# Connectors.net
KiCad netlist of a schematic drawn in Altium Designer
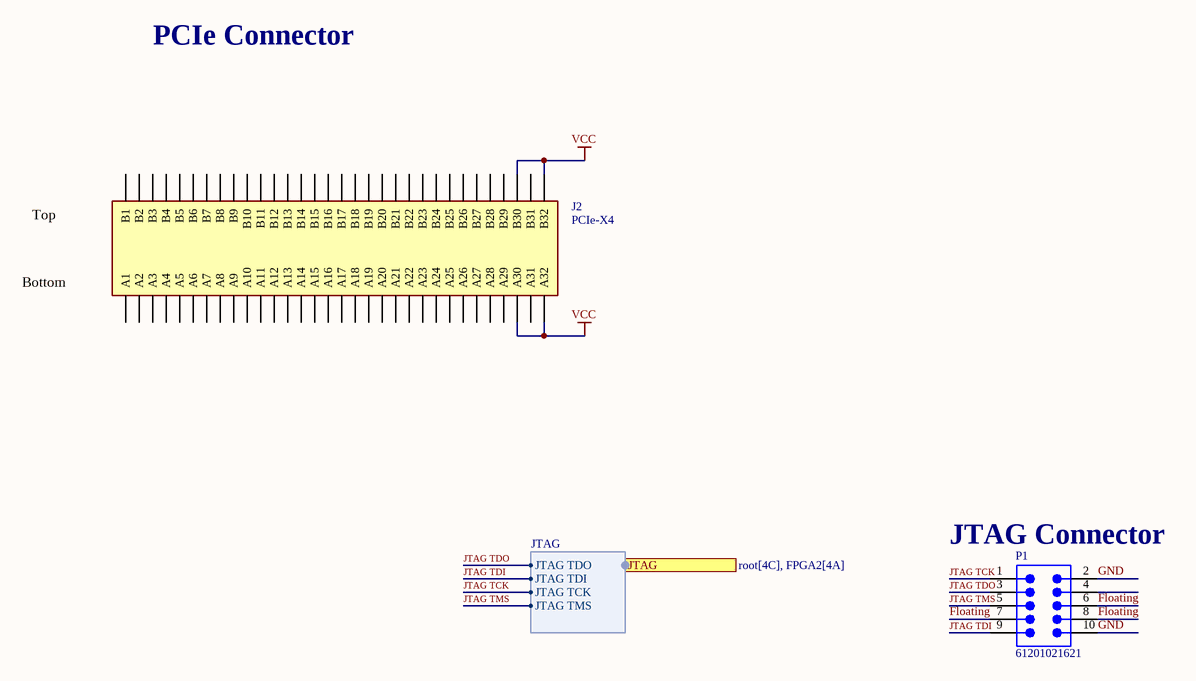
[diagram p0: Connectors.SchDoc]

(export (version "E")
  (design (tool "Eeschema 10.0.6"))
  (components
    (comp (ref "J2")
      (value "PCIe-X4")
      (footprint "BUS_PCIexpress_x4")
      (libsource (lib "FC") (part "PCIe-X4"))
    )
    (comp (ref "P1")
      (value "61201021621")
      (footprint "61201021621")
      (libsource (lib "Altium Content Vault") (part "Header_Male_2R_10P"))
    )
  )
  (nets
    (net (code "2") (name "/Floating") (class "Default")
      (node (ref "P1") (pin "6") (pinfunction "6_6") (pintype "passive"))
      (node (ref "P1") (pin "7") (pinfunction "7_7") (pintype "passive"))
      (node (ref "P1") (pin "8") (pinfunction "8_8") (pintype "passive"))
    )
    (net (code "3") (name "/GND") (class "Default")
      (node (ref "P1") (pin "10") (pinfunction "10_10") (pintype "passive"))
      (node (ref "P1") (pin "2") (pinfunction "2_2") (pintype "passive"))
    )
    (net (code "4") (name "/JTAG TCK") (class "Default")
      (node (ref "P1") (pin "1") (pinfunction "1_1") (pintype "passive"))
    )
    (net (code "5") (name "/JTAG TDI") (class "Default")
      (node (ref "P1") (pin "9") (pinfunction "9_9") (pintype "passive"))
    )
    (net (code "6") (name "/JTAG TDO") (class "Default")
      (node (ref "P1") (pin "3") (pinfunction "3_3") (pintype "passive"))
    )
    (net (code "7") (name "/JTAG TMS") (class "Default")
      (node (ref "P1") (pin "5") (pinfunction "5_5") (pintype "passive"))
    )
    (net (code "9") (name "VCC") (class "Default")
      (node (ref "J2") (pin "A30") (pinfunction "A30_A30") (pintype "passive"))
      (node (ref "J2") (pin "A32") (pinfunction "A32_A32") (pintype "passive"))
      (node (ref "J2") (pin "B30") (pinfunction "B30_B30") (pintype "passive"))
      (node (ref "J2") (pin "B32") (pinfunction "B32_B32") (pintype "passive"))
    )
    (net (code "10") (name "unconnected-(J2-PadA1)") (class "Default")
      (node (ref "J2") (pin "A1") (pinfunction "A1_A1") (pintype "passive"))
    )
    (net (code "11") (name "unconnected-(J2-PadA2)") (class "Default")
      (node (ref "J2") (pin "A2") (pinfunction "A2_A2") (pintype "passive"))
    )
    (net (code "12") (name "unconnected-(J2-PadA3)") (class "Default")
      (node (ref "J2") (pin "A3") (pinfunction "A3_A3") (pintype "passive"))
    )
    (net (code "13") (name "unconnected-(J2-PadA4)") (class "Default")
      (node (ref "J2") (pin "A4") (pinfunction "A4_A4") (pintype "passive"))
    )
    (net (code "14") (name "unconnected-(J2-PadA5)") (class "Default")
      (node (ref "J2") (pin "A5") (pinfunction "A5_A5") (pintype "passive"))
    )
    (net (code "15") (name "unconnected-(J2-PadA6)") (class "Default")
      (node (ref "J2") (pin "A6") (pinfunction "A6_A6") (pintype "passive"))
    )
    (net (code "16") (name "unconnected-(J2-PadA7)") (class "Default")
      (node (ref "J2") (pin "A7") (pinfunction "A7_A7") (pintype "passive"))
    )
    (net (code "17") (name "unconnected-(J2-PadA8)") (class "Default")
      (node (ref "J2") (pin "A8") (pinfunction "A8_A8") (pintype "passive"))
    )
    (net (code "18") (name "unconnected-(J2-PadA9)") (class "Default")
      (node (ref "J2") (pin "A9") (pinfunction "A9_A9") (pintype "passive"))
    )
    (net (code "19") (name "unconnected-(J2-PadA10)") (class "Default")
      (node (ref "J2") (pin "A10") (pinfunction "A10_A10") (pintype "passive"))
    )
    (net (code "20") (name "unconnected-(J2-PadA11)") (class "Default")
      (node (ref "J2") (pin "A11") (pinfunction "A11_A11") (pintype "passive"))
    )
    (net (code "21") (name "unconnected-(J2-PadA12)") (class "Default")
      (node (ref "J2") (pin "A12") (pinfunction "A12_A12") (pintype "passive"))
    )
    (net (code "22") (name "unconnected-(J2-PadA13)") (class "Default")
      (node (ref "J2") (pin "A13") (pinfunction "A13_A13") (pintype "passive"))
    )
    (net (code "23") (name "unconnected-(J2-PadA14)") (class "Default")
      (node (ref "J2") (pin "A14") (pinfunction "A14_A14") (pintype "passive"))
    )
    (net (code "24") (name "unconnected-(J2-PadA15)") (class "Default")
      (node (ref "J2") (pin "A15") (pinfunction "A15_A15") (pintype "passive"))
    )
    (net (code "25") (name "unconnected-(J2-PadA16)") (class "Default")
      (node (ref "J2") (pin "A16") (pinfunction "A16_A16") (pintype "passive"))
    )
    (net (code "26") (name "unconnected-(J2-PadA17)") (class "Default")
      (node (ref "J2") (pin "A17") (pinfunction "A17_A17") (pintype "passive"))
    )
    (net (code "27") (name "unconnected-(J2-PadA18)") (class "Default")
      (node (ref "J2") (pin "A18") (pinfunction "A18_A18") (pintype "passive"))
    )
    (net (code "28") (name "unconnected-(J2-PadA19)") (class "Default")
      (node (ref "J2") (pin "A19") (pinfunction "A19_A19") (pintype "passive"))
    )
    (net (code "29") (name "unconnected-(J2-PadA20)") (class "Default")
      (node (ref "J2") (pin "A20") (pinfunction "A20_A20") (pintype "passive"))
    )
    (net (code "30") (name "unconnected-(J2-PadA21)") (class "Default")
      (node (ref "J2") (pin "A21") (pinfunction "A21_A21") (pintype "passive"))
    )
    (net (code "31") (name "unconnected-(J2-PadA22)") (class "Default")
      (node (ref "J2") (pin "A22") (pinfunction "A22_A22") (pintype "passive"))
    )
    (net (code "32") (name "unconnected-(J2-PadA23)") (class "Default")
      (node (ref "J2") (pin "A23") (pinfunction "A23_A23") (pintype "passive"))
    )
    (net (code "33") (name "unconnected-(J2-PadA24)") (class "Default")
      (node (ref "J2") (pin "A24") (pinfunction "A24_A24") (pintype "passive"))
    )
    (net (code "34") (name "unconnected-(J2-PadA25)") (class "Default")
      (node (ref "J2") (pin "A25") (pinfunction "A25_A25") (pintype "passive"))
    )
    (net (code "35") (name "unconnected-(J2-PadA26)") (class "Default")
      (node (ref "J2") (pin "A26") (pinfunction "A26_A26") (pintype "passive"))
    )
    (net (code "36") (name "unconnected-(J2-PadA27)") (class "Default")
      (node (ref "J2") (pin "A27") (pinfunction "A27_A27") (pintype "passive"))
    )
    (net (code "37") (name "unconnected-(J2-PadA28)") (class "Default")
      (node (ref "J2") (pin "A28") (pinfunction "A28_A28") (pintype "passive"))
    )
    (net (code "38") (name "unconnected-(J2-PadA29)") (class "Default")
      (node (ref "J2") (pin "A29") (pinfunction "A29_A29") (pintype "passive"))
    )
    (net (code "39") (name "unconnected-(J2-PadA31)") (class "Default")
      (node (ref "J2") (pin "A31") (pinfunction "A31_A31") (pintype "passive"))
    )
    (net (code "40") (name "unconnected-(J2-PadB1)") (class "Default")
      (node (ref "J2") (pin "B1") (pinfunction "B1_B1") (pintype "passive"))
    )
    (net (code "41") (name "unconnected-(J2-PadB2)") (class "Default")
      (node (ref "J2") (pin "B2") (pinfunction "B2_B2") (pintype "passive"))
    )
    (net (code "42") (name "unconnected-(J2-PadB3)") (class "Default")
      (node (ref "J2") (pin "B3") (pinfunction "B3_B3") (pintype "passive"))
    )
    (net (code "43") (name "unconnected-(J2-PadB4)") (class "Default")
      (node (ref "J2") (pin "B4") (pinfunction "B4_B4") (pintype "passive"))
    )
    (net (code "44") (name "unconnected-(J2-PadB5)") (class "Default")
      (node (ref "J2") (pin "B5") (pinfunction "B5_B5") (pintype "passive"))
    )
    (net (code "45") (name "unconnected-(J2-PadB6)") (class "Default")
      (node (ref "J2") (pin "B6") (pinfunction "B6_B6") (pintype "passive"))
    )
    (net (code "46") (name "unconnected-(J2-PadB7)") (class "Default")
      (node (ref "J2") (pin "B7") (pinfunction "B7_B7") (pintype "passive"))
    )
    (net (code "47") (name "unconnected-(J2-PadB8)") (class "Default")
      (node (ref "J2") (pin "B8") (pinfunction "B8_B8") (pintype "passive"))
    )
    (net (code "48") (name "unconnected-(J2-PadB9)") (class "Default")
      (node (ref "J2") (pin "B9") (pinfunction "B9_B9") (pintype "passive"))
    )
    (net (code "49") (name "unconnected-(J2-PadB10)") (class "Default")
      (node (ref "J2") (pin "B10") (pinfunction "B10_B10") (pintype "passive"))
    )
    (net (code "50") (name "unconnected-(J2-PadB11)") (class "Default")
      (node (ref "J2") (pin "B11") (pinfunction "B11_B11") (pintype "passive"))
    )
    (net (code "51") (name "unconnected-(J2-PadB12)") (class "Default")
      (node (ref "J2") (pin "B12") (pinfunction "B12_B12") (pintype "passive"))
    )
    (net (code "52") (name "unconnected-(J2-PadB13)") (class "Default")
      (node (ref "J2") (pin "B13") (pinfunction "B13_B13") (pintype "passive"))
    )
    (net (code "53") (name "unconnected-(J2-PadB14)") (class "Default")
      (node (ref "J2") (pin "B14") (pinfunction "B14_B14") (pintype "passive"))
    )
    (net (code "54") (name "unconnected-(J2-PadB15)") (class "Default")
      (node (ref "J2") (pin "B15") (pinfunction "B15_B15") (pintype "passive"))
    )
    (net (code "55") (name "unconnected-(J2-PadB16)") (class "Default")
      (node (ref "J2") (pin "B16") (pinfunction "B16_B16") (pintype "passive"))
    )
    (net (code "56") (name "unconnected-(J2-PadB17)") (class "Default")
      (node (ref "J2") (pin "B17") (pinfunction "B17_B17") (pintype "passive"))
    )
    (net (code "57") (name "unconnected-(J2-PadB18)") (class "Default")
      (node (ref "J2") (pin "B18") (pinfunction "B18_B18") (pintype "passive"))
    )
    (net (code "58") (name "unconnected-(J2-PadB19)") (class "Default")
      (node (ref "J2") (pin "B19") (pinfunction "B19_B19") (pintype "passive"))
    )
    (net (code "59") (name "unconnected-(J2-PadB20)") (class "Default")
      (node (ref "J2") (pin "B20") (pinfunction "B20_B20") (pintype "passive"))
    )
    (net (code "60") (name "unconnected-(J2-PadB21)") (class "Default")
      (node (ref "J2") (pin "B21") (pinfunction "B21_B21") (pintype "passive"))
    )
    (net (code "61") (name "unconnected-(J2-PadB22)") (class "Default")
      (node (ref "J2") (pin "B22") (pinfunction "B22_B22") (pintype "passive"))
    )
    (net (code "62") (name "unconnected-(J2-PadB23)") (class "Default")
      (node (ref "J2") (pin "B23") (pinfunction "B23_B23") (pintype "passive"))
    )
    (net (code "63") (name "unconnected-(J2-PadB24)") (class "Default")
      (node (ref "J2") (pin "B24") (pinfunction "B24_B24") (pintype "passive"))
    )
    (net (code "64") (name "unconnected-(J2-PadB25)") (class "Default")
      (node (ref "J2") (pin "B25") (pinfunction "B25_B25") (pintype "passive"))
    )
    (net (code "65") (name "unconnected-(J2-PadB26)") (class "Default")
      (node (ref "J2") (pin "B26") (pinfunction "B26_B26") (pintype "passive"))
    )
    (net (code "66") (name "unconnected-(J2-PadB27)") (class "Default")
      (node (ref "J2") (pin "B27") (pinfunction "B27_B27") (pintype "passive"))
    )
    (net (code "67") (name "unconnected-(J2-PadB28)") (class "Default")
      (node (ref "J2") (pin "B28") (pinfunction "B28_B28") (pintype "passive"))
    )
    (net (code "68") (name "unconnected-(J2-PadB29)") (class "Default")
      (node (ref "J2") (pin "B29") (pinfunction "B29_B29") (pintype "passive"))
    )
    (net (code "69") (name "unconnected-(J2-PadB31)") (class "Default")
      (node (ref "J2") (pin "B31") (pinfunction "B31_B31") (pintype "passive"))
    )
    (net (code "70") (name "unconnected-(P1-Pad4)") (class "Default")
      (node (ref "P1") (pin "4") (pinfunction "4_4") (pintype "passive"))
    )
  )
)
